# USBPower.net
KiCad netlist of a schematic drawn in EAGLE
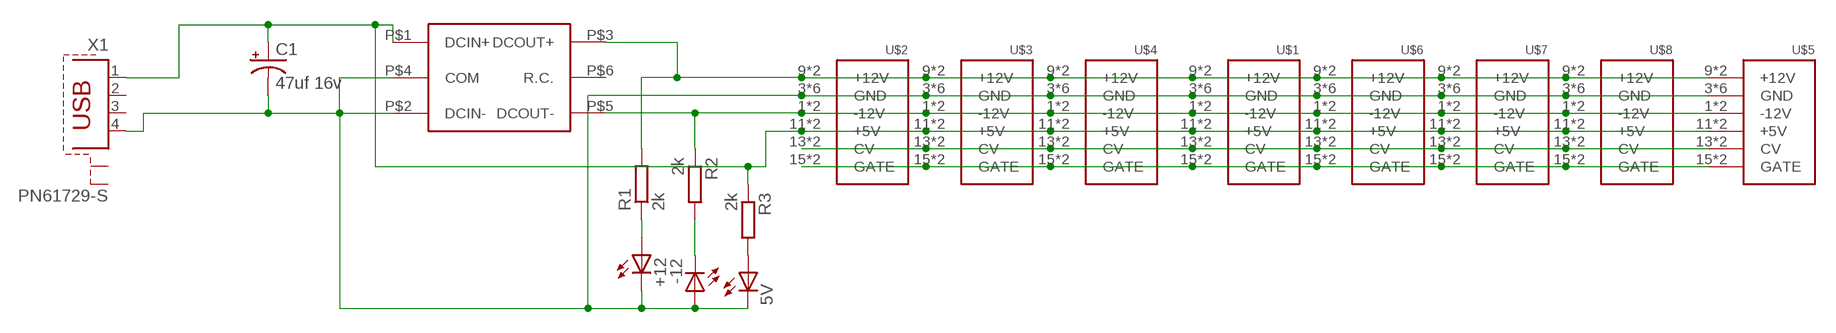
[diagram p0: schematic, sheet 1]

(export (version "E")
  (design (tool "Eeschema 10.0.6"))
  (components
    (comp (ref "+12")
      (value "LED3MM")
      (footprint "eagle-import:LED3MM")
      (libsource (lib "eagle-import") (part "LED3MM"))
    )
    (comp (ref "-12")
      (value "LED3MM")
      (footprint "eagle-import:LED3MM")
      (libsource (lib "eagle-import") (part "LED3MM"))
    )
    (comp (ref "5V")
      (value "LED3MM")
      (footprint "eagle-import:LED3MM")
      (libsource (lib "eagle-import") (part "LED3MM"))
    )
    (comp (ref "C1")
      (value "47uf 16v")
      (footprint "eagle-import:050_020")
      (libsource (lib "eagle-import") (part "050"))
    )
    (comp (ref "R1")
      (value "2k")
      (footprint "eagle-import:7MM_RESISTOR")
      (libsource (lib "eagle-import") (part "RESISTOR7MM"))
    )
    (comp (ref "R2")
      (value "2k")
      (footprint "eagle-import:7MM_RESISTOR")
      (libsource (lib "eagle-import") (part "RESISTOR7MM"))
    )
    (comp (ref "R3")
      (value "2k")
      (footprint "eagle-import:7MM_RESISTOR")
      (libsource (lib "eagle-import") (part "RESISTOR7MM"))
    )
    (comp (ref "U$1")
      (value "POWER")
      (footprint "eagle-import:POWER_16")
      (libsource (lib "eagle-import") (part "POWER"))
    )
    (comp (ref "U$2")
      (value "POWER")
      (footprint "eagle-import:POWER_16")
      (libsource (lib "eagle-import") (part "POWER"))
    )
    (comp (ref "U$3")
      (value "POWER")
      (footprint "eagle-import:POWER_16")
      (libsource (lib "eagle-import") (part "POWER"))
    )
    (comp (ref "U$4")
      (value "POWER")
      (footprint "eagle-import:POWER_16")
      (libsource (lib "eagle-import") (part "POWER"))
    )
    (comp (ref "U$5")
      (value "POWER")
      (footprint "eagle-import:POWER_16")
      (libsource (lib "eagle-import") (part "POWER"))
    )
    (comp (ref "U$6")
      (value "POWER")
      (footprint "eagle-import:POWER_16")
      (libsource (lib "eagle-import") (part "POWER"))
    )
    (comp (ref "U$7")
      (value "POWER")
      (footprint "eagle-import:POWER_16")
      (libsource (lib "eagle-import") (part "POWER"))
    )
    (comp (ref "U$8")
      (value "POWER")
      (footprint "eagle-import:POWER_16")
      (libsource (lib "eagle-import") (part "POWER"))
    )
    (comp (ref "U$9")
      (value "DKM-10")
      (footprint "eagle-import:1X1")
      (libsource (lib "eagle-import") (part "DKM-10"))
    )
    (comp (ref "X1")
      (value "PN61729-S")
      (footprint "eagle-import:PN61729-S")
      (libsource (lib "eagle-import") (part "PN61729-S"))
    )
  )
  (nets
    (net (code "1") (name "Net-(+12-C)") (class "Default")
      (node (ref "+12") (pin "K") (pinfunction "C_K") (pintype "passive"))
      (node (ref "-12") (pin "A") (pinfunction "A_A") (pintype "passive"))
      (node (ref "5V") (pin "K") (pinfunction "C_K") (pintype "passive"))
      (node (ref "C1") (pin "-") (pinfunction "-_-") (pintype "passive"))
      (node (ref "U$1") (pin "3") (pinfunction "GND_3") (pintype "bidirectional"))
      (node (ref "U$1") (pin "4") (pinfunction "GND_4") (pintype "bidirectional"))
      (node (ref "U$1") (pin "5") (pinfunction "GND_5") (pintype "bidirectional"))
      (node (ref "U$1") (pin "6") (pinfunction "GND_6") (pintype "bidirectional"))
      (node (ref "U$1") (pin "7") (pinfunction "GND_7") (pintype "bidirectional"))
      (node (ref "U$1") (pin "8") (pinfunction "GND_8") (pintype "bidirectional"))
      (node (ref "U$2") (pin "3") (pinfunction "GND_3") (pintype "bidirectional"))
      (node (ref "U$2") (pin "4") (pinfunction "GND_4") (pintype "bidirectional"))
      (node (ref "U$2") (pin "5") (pinfunction "GND_5") (pintype "bidirectional"))
      (node (ref "U$2") (pin "6") (pinfunction "GND_6") (pintype "bidirectional"))
      (node (ref "U$2") (pin "7") (pinfunction "GND_7") (pintype "bidirectional"))
      (node (ref "U$2") (pin "8") (pinfunction "GND_8") (pintype "bidirectional"))
      (node (ref "U$3") (pin "3") (pinfunction "GND_3") (pintype "bidirectional"))
      (node (ref "U$3") (pin "4") (pinfunction "GND_4") (pintype "bidirectional"))
      (node (ref "U$3") (pin "5") (pinfunction "GND_5") (pintype "bidirectional"))
      (node (ref "U$3") (pin "6") (pinfunction "GND_6") (pintype "bidirectional"))
      (node (ref "U$3") (pin "7") (pinfunction "GND_7") (pintype "bidirectional"))
      (node (ref "U$3") (pin "8") (pinfunction "GND_8") (pintype "bidirectional"))
      (node (ref "U$4") (pin "3") (pinfunction "GND_3") (pintype "bidirectional"))
      (node (ref "U$4") (pin "4") (pinfunction "GND_4") (pintype "bidirectional"))
      (node (ref "U$4") (pin "5") (pinfunction "GND_5") (pintype "bidirectional"))
      (node (ref "U$4") (pin "6") (pinfunction "GND_6") (pintype "bidirectional"))
      (node (ref "U$4") (pin "7") (pinfunction "GND_7") (pintype "bidirectional"))
      (node (ref "U$4") (pin "8") (pinfunction "GND_8") (pintype "bidirectional"))
      (node (ref "U$5") (pin "3") (pinfunction "GND_3") (pintype "bidirectional"))
      (node (ref "U$5") (pin "4") (pinfunction "GND_4") (pintype "bidirectional"))
      (node (ref "U$5") (pin "5") (pinfunction "GND_5") (pintype "bidirectional"))
      (node (ref "U$5") (pin "6") (pinfunction "GND_6") (pintype "bidirectional"))
      (node (ref "U$5") (pin "7") (pinfunction "GND_7") (pintype "bidirectional"))
      (node (ref "U$5") (pin "8") (pinfunction "GND_8") (pintype "bidirectional"))
      (node (ref "U$6") (pin "3") (pinfunction "GND_3") (pintype "bidirectional"))
      (node (ref "U$6") (pin "4") (pinfunction "GND_4") (pintype "bidirectional"))
      (node (ref "U$6") (pin "5") (pinfunction "GND_5") (pintype "bidirectional"))
      (node (ref "U$6") (pin "6") (pinfunction "GND_6") (pintype "bidirectional"))
      (node (ref "U$6") (pin "7") (pinfunction "GND_7") (pintype "bidirectional"))
      (node (ref "U$6") (pin "8") (pinfunction "GND_8") (pintype "bidirectional"))
      (node (ref "U$7") (pin "3") (pinfunction "GND_3") (pintype "bidirectional"))
      (node (ref "U$7") (pin "4") (pinfunction "GND_4") (pintype "bidirectional"))
      (node (ref "U$7") (pin "5") (pinfunction "GND_5") (pintype "bidirectional"))
      (node (ref "U$7") (pin "6") (pinfunction "GND_6") (pintype "bidirectional"))
      (node (ref "U$7") (pin "7") (pinfunction "GND_7") (pintype "bidirectional"))
      (node (ref "U$7") (pin "8") (pinfunction "GND_8") (pintype "bidirectional"))
      (node (ref "U$8") (pin "3") (pinfunction "GND_3") (pintype "bidirectional"))
      (node (ref "U$8") (pin "4") (pinfunction "GND_4") (pintype "bidirectional"))
      (node (ref "U$8") (pin "5") (pinfunction "GND_5") (pintype "bidirectional"))
      (node (ref "U$8") (pin "6") (pinfunction "GND_6") (pintype "bidirectional"))
      (node (ref "U$8") (pin "7") (pinfunction "GND_7") (pintype "bidirectional"))
      (node (ref "U$8") (pin "8") (pinfunction "GND_8") (pintype "bidirectional"))
      (node (ref "U$9") (pin "P$2") (pinfunction "DCIN-_P$2") (pintype "input"))
      (node (ref "U$9") (pin "P$4") (pinfunction "COM_P$4") (pintype "bidirectional"))
      (node (ref "X1") (pin "4") (pinfunction "4_4") (pintype "passive"))
    )
    (net (code "2") (name "Net-(+12-PadA)") (class "Default")
      (node (ref "+12") (pin "A") (pinfunction "A_A") (pintype "passive"))
      (node (ref "R1") (pin "1") (pinfunction "1_1") (pintype "passive"))
    )
    (net (code "3") (name "Net-(-12-C)") (class "Default")
      (node (ref "-12") (pin "K") (pinfunction "C_K") (pintype "passive"))
      (node (ref "R2") (pin "2") (pinfunction "2_2") (pintype "passive"))
    )
    (net (code "4") (name "Net-(5V-PadA)") (class "Default")
      (node (ref "5V") (pin "A") (pinfunction "A_A") (pintype "passive"))
      (node (ref "R3") (pin "2") (pinfunction "2_2") (pintype "passive"))
    )
    (net (code "5") (name "Net-(U$1-CV-Pad13)") (class "Default")
      (node (ref "U$1") (pin "13") (pinfunction "CV_13") (pintype "bidirectional"))
      (node (ref "U$1") (pin "14") (pinfunction "CV_14") (pintype "bidirectional"))
      (node (ref "U$2") (pin "13") (pinfunction "CV_13") (pintype "bidirectional"))
      (node (ref "U$2") (pin "14") (pinfunction "CV_14") (pintype "bidirectional"))
      (node (ref "U$3") (pin "13") (pinfunction "CV_13") (pintype "bidirectional"))
      (node (ref "U$3") (pin "14") (pinfunction "CV_14") (pintype "bidirectional"))
      (node (ref "U$4") (pin "13") (pinfunction "CV_13") (pintype "bidirectional"))
      (node (ref "U$4") (pin "14") (pinfunction "CV_14") (pintype "bidirectional"))
      (node (ref "U$5") (pin "13") (pinfunction "CV_13") (pintype "bidirectional"))
      (node (ref "U$5") (pin "14") (pinfunction "CV_14") (pintype "bidirectional"))
      (node (ref "U$6") (pin "13") (pinfunction "CV_13") (pintype "bidirectional"))
      (node (ref "U$6") (pin "14") (pinfunction "CV_14") (pintype "bidirectional"))
      (node (ref "U$7") (pin "13") (pinfunction "CV_13") (pintype "bidirectional"))
      (node (ref "U$7") (pin "14") (pinfunction "CV_14") (pintype "bidirectional"))
      (node (ref "U$8") (pin "13") (pinfunction "CV_13") (pintype "bidirectional"))
      (node (ref "U$8") (pin "14") (pinfunction "CV_14") (pintype "bidirectional"))
    )
    (net (code "6") (name "Net-(U$1-GATE-Pad15)") (class "Default")
      (node (ref "U$1") (pin "15") (pinfunction "GATE_15") (pintype "bidirectional"))
      (node (ref "U$1") (pin "16") (pinfunction "GATE_16") (pintype "bidirectional"))
      (node (ref "U$2") (pin "15") (pinfunction "GATE_15") (pintype "bidirectional"))
      (node (ref "U$2") (pin "16") (pinfunction "GATE_16") (pintype "bidirectional"))
      (node (ref "U$3") (pin "15") (pinfunction "GATE_15") (pintype "bidirectional"))
      (node (ref "U$3") (pin "16") (pinfunction "GATE_16") (pintype "bidirectional"))
      (node (ref "U$4") (pin "15") (pinfunction "GATE_15") (pintype "bidirectional"))
      (node (ref "U$4") (pin "16") (pinfunction "GATE_16") (pintype "bidirectional"))
      (node (ref "U$5") (pin "15") (pinfunction "GATE_15") (pintype "bidirectional"))
      (node (ref "U$5") (pin "16") (pinfunction "GATE_16") (pintype "bidirectional"))
      (node (ref "U$6") (pin "15") (pinfunction "GATE_15") (pintype "bidirectional"))
      (node (ref "U$6") (pin "16") (pinfunction "GATE_16") (pintype "bidirectional"))
      (node (ref "U$7") (pin "15") (pinfunction "GATE_15") (pintype "bidirectional"))
      (node (ref "U$7") (pin "16") (pinfunction "GATE_16") (pintype "bidirectional"))
      (node (ref "U$8") (pin "15") (pinfunction "GATE_15") (pintype "bidirectional"))
      (node (ref "U$8") (pin "16") (pinfunction "GATE_16") (pintype "bidirectional"))
    )
    (net (code "7") (name "Net-(U$9-DCIN+)") (class "Default")
      (node (ref "C1") (pin "+") (pinfunction "+_+") (pintype "passive"))
      (node (ref "R3") (pin "1") (pinfunction "1_1") (pintype "passive"))
      (node (ref "U$1") (pin "11") (pinfunction "+5V_11") (pintype "bidirectional"))
      (node (ref "U$1") (pin "12") (pinfunction "+5V_12") (pintype "bidirectional"))
      (node (ref "U$2") (pin "11") (pinfunction "+5V_11") (pintype "bidirectional"))
      (node (ref "U$2") (pin "12") (pinfunction "+5V_12") (pintype "bidirectional"))
      (node (ref "U$3") (pin "11") (pinfunction "+5V_11") (pintype "bidirectional"))
      (node (ref "U$3") (pin "12") (pinfunction "+5V_12") (pintype "bidirectional"))
      (node (ref "U$4") (pin "11") (pinfunction "+5V_11") (pintype "bidirectional"))
      (node (ref "U$4") (pin "12") (pinfunction "+5V_12") (pintype "bidirectional"))
      (node (ref "U$5") (pin "11") (pinfunction "+5V_11") (pintype "bidirectional"))
      (node (ref "U$5") (pin "12") (pinfunction "+5V_12") (pintype "bidirectional"))
      (node (ref "U$6") (pin "11") (pinfunction "+5V_11") (pintype "bidirectional"))
      (node (ref "U$6") (pin "12") (pinfunction "+5V_12") (pintype "bidirectional"))
      (node (ref "U$7") (pin "11") (pinfunction "+5V_11") (pintype "bidirectional"))
      (node (ref "U$7") (pin "12") (pinfunction "+5V_12") (pintype "bidirectional"))
      (node (ref "U$8") (pin "11") (pinfunction "+5V_11") (pintype "bidirectional"))
      (node (ref "U$8") (pin "12") (pinfunction "+5V_12") (pintype "bidirectional"))
      (node (ref "U$9") (pin "P$1") (pinfunction "DCIN+_P$1") (pintype "input"))
      (node (ref "X1") (pin "1") (pinfunction "1_1") (pintype "passive"))
    )
    (net (code "8") (name "Net-(U$9-DCOUT+)") (class "Default")
      (node (ref "R1") (pin "2") (pinfunction "2_2") (pintype "passive"))
      (node (ref "U$1") (pin "10") (pinfunction "+12V_10") (pintype "bidirectional"))
      (node (ref "U$1") (pin "9") (pinfunction "+12V_9") (pintype "bidirectional"))
      (node (ref "U$2") (pin "10") (pinfunction "+12V_10") (pintype "bidirectional"))
      (node (ref "U$2") (pin "9") (pinfunction "+12V_9") (pintype "bidirectional"))
      (node (ref "U$3") (pin "10") (pinfunction "+12V_10") (pintype "bidirectional"))
      (node (ref "U$3") (pin "9") (pinfunction "+12V_9") (pintype "bidirectional"))
      (node (ref "U$4") (pin "10") (pinfunction "+12V_10") (pintype "bidirectional"))
      (node (ref "U$4") (pin "9") (pinfunction "+12V_9") (pintype "bidirectional"))
      (node (ref "U$5") (pin "10") (pinfunction "+12V_10") (pintype "bidirectional"))
      (node (ref "U$5") (pin "9") (pinfunction "+12V_9") (pintype "bidirectional"))
      (node (ref "U$6") (pin "10") (pinfunction "+12V_10") (pintype "bidirectional"))
      (node (ref "U$6") (pin "9") (pinfunction "+12V_9") (pintype "bidirectional"))
      (node (ref "U$7") (pin "10") (pinfunction "+12V_10") (pintype "bidirectional"))
      (node (ref "U$7") (pin "9") (pinfunction "+12V_9") (pintype "bidirectional"))
      (node (ref "U$8") (pin "10") (pinfunction "+12V_10") (pintype "bidirectional"))
      (node (ref "U$8") (pin "9") (pinfunction "+12V_9") (pintype "bidirectional"))
      (node (ref "U$9") (pin "P$3") (pinfunction "DCOUT+_P$3") (pintype "output"))
    )
    (net (code "9") (name "Net-(U$9-DCOUT-)") (class "Default")
      (node (ref "R2") (pin "1") (pinfunction "1_1") (pintype "passive"))
      (node (ref "U$1") (pin "1") (pinfunction "-12V_1") (pintype "bidirectional"))
      (node (ref "U$1") (pin "2") (pinfunction "-12V_2") (pintype "bidirectional"))
      (node (ref "U$2") (pin "1") (pinfunction "-12V_1") (pintype "bidirectional"))
      (node (ref "U$2") (pin "2") (pinfunction "-12V_2") (pintype "bidirectional"))
      (node (ref "U$3") (pin "1") (pinfunction "-12V_1") (pintype "bidirectional"))
      (node (ref "U$3") (pin "2") (pinfunction "-12V_2") (pintype "bidirectional"))
      (node (ref "U$4") (pin "1") (pinfunction "-12V_1") (pintype "bidirectional"))
      (node (ref "U$4") (pin "2") (pinfunction "-12V_2") (pintype "bidirectional"))
      (node (ref "U$5") (pin "1") (pinfunction "-12V_1") (pintype "bidirectional"))
      (node (ref "U$5") (pin "2") (pinfunction "-12V_2") (pintype "bidirectional"))
      (node (ref "U$6") (pin "1") (pinfunction "-12V_1") (pintype "bidirectional"))
      (node (ref "U$6") (pin "2") (pinfunction "-12V_2") (pintype "bidirectional"))
      (node (ref "U$7") (pin "1") (pinfunction "-12V_1") (pintype "bidirectional"))
      (node (ref "U$7") (pin "2") (pinfunction "-12V_2") (pintype "bidirectional"))
      (node (ref "U$8") (pin "1") (pinfunction "-12V_1") (pintype "bidirectional"))
      (node (ref "U$8") (pin "2") (pinfunction "-12V_2") (pintype "bidirectional"))
      (node (ref "U$9") (pin "P$5") (pinfunction "DCOUT-_P$5") (pintype "output"))
    )
    (net (code "10") (name "unconnected-(U$9-R.C.-PadP$6)") (class "Default")
      (node (ref "U$9") (pin "P$6") (pinfunction "R.C._P$6") (pintype "bidirectional"))
    )
    (net (code "11") (name "unconnected-(X1-Pad2)") (class "Default")
      (node (ref "X1") (pin "2") (pinfunction "2_2") (pintype "passive"))
    )
    (net (code "12") (name "unconnected-(X1-Pad3)") (class "Default")
      (node (ref "X1") (pin "3") (pinfunction "3_3") (pintype "passive"))
    )
    (net (code "13") (name "unconnected-(X1-PadS1)") (class "Default")
      (node (ref "X1") (pin "S1") (pinfunction "S1_S1") (pintype "passive"))
    )
    (net (code "14") (name "unconnected-(X1-PadS2)") (class "Default")
      (node (ref "X1") (pin "S2") (pinfunction "S2_S2") (pintype "passive"))
    )
  )
)
